# FTDI_GT16.net
KiCad netlist of a schematic drawn in EAGLE
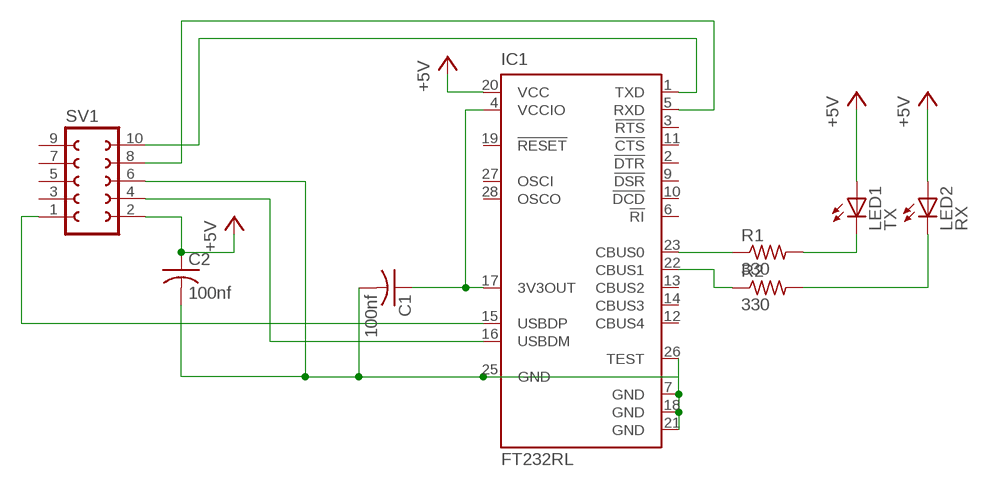
[diagram p0: schematic, sheet 1]

(export (version "E")
  (design (tool "Eeschema 10.0.6"))
  (components
    (comp (ref "C1")
      (value "100nf")
      (footprint "eagle-import:C0805")
      (libsource (lib "eagle-import") (part "C-USC0805"))
    )
    (comp (ref "C2")
      (value "100nf")
      (footprint "eagle-import:C0805")
      (libsource (lib "eagle-import") (part "C-USC0805"))
    )
    (comp (ref "IC1")
      (value "FT232RL")
      (footprint "eagle-import:SSOP28")
      (libsource (lib "eagle-import") (part "FT232RL"))
    )
    (comp (ref "LED1")
      (value "TX")
      (footprint "eagle-import:CHIPLED_0805")
      (libsource (lib "eagle-import") (part "LEDCHIPLED_0805"))
    )
    (comp (ref "LED2")
      (value "RX")
      (footprint "eagle-import:CHIPLED_0805")
      (libsource (lib "eagle-import") (part "LEDCHIPLED_0805"))
    )
    (comp (ref "R1")
      (value "330")
      (footprint "eagle-import:R0805")
      (libsource (lib "eagle-import") (part "R-US_R0805"))
    )
    (comp (ref "R2")
      (value "330")
      (footprint "eagle-import:R0805")
      (libsource (lib "eagle-import") (part "R-US_R0805"))
    )
    (comp (ref "SV1")
      (value "FE05-2")
      (footprint "eagle-import:FE05-2")
      (libsource (lib "eagle-import") (part "FE05-2"))
    )
  )
  (nets
    (net (code "1") (name "+5V") (class "Default")
      (node (ref "C2") (pin "1") (pinfunction "1_1") (pintype "passive"))
      (node (ref "IC1") (pin "20") (pinfunction "VCC_20") (pintype "power_in"))
      (node (ref "LED1") (pin "A") (pinfunction "A_A") (pintype "passive"))
      (node (ref "LED2") (pin "A") (pinfunction "A_A") (pintype "passive"))
      (node (ref "SV1") (pin "2") (pinfunction "2_2") (pintype "passive"))
    )
    (net (code "2") (name "Net-(IC1-3V3OUT)") (class "Default")
      (node (ref "C1") (pin "1") (pinfunction "1_1") (pintype "passive"))
      (node (ref "IC1") (pin "17") (pinfunction "3V3OUT_17") (pintype "output"))
      (node (ref "IC1") (pin "4") (pinfunction "VCCIO_4") (pintype "power_in"))
    )
    (net (code "3") (name "Net-(IC1-CBUS0)") (class "Default")
      (node (ref "IC1") (pin "23") (pinfunction "CBUS0_23") (pintype "bidirectional"))
      (node (ref "R1") (pin "1") (pinfunction "1_1") (pintype "passive"))
    )
    (net (code "4") (name "Net-(IC1-CBUS1)") (class "Default")
      (node (ref "IC1") (pin "22") (pinfunction "CBUS1_22") (pintype "bidirectional"))
      (node (ref "R2") (pin "1") (pinfunction "1_1") (pintype "passive"))
    )
    (net (code "5") (name "Net-(IC1-RXD)") (class "Default")
      (node (ref "IC1") (pin "5") (pinfunction "RXD_5") (pintype "input"))
      (node (ref "SV1") (pin "8") (pinfunction "8_8") (pintype "passive"))
    )
    (net (code "6") (name "Net-(IC1-TEST)") (class "Default")
      (node (ref "C1") (pin "2") (pinfunction "2_2") (pintype "passive"))
      (node (ref "C2") (pin "2") (pinfunction "2_2") (pintype "passive"))
      (node (ref "IC1") (pin "18") (pinfunction "GND_18") (pintype "power_in"))
      (node (ref "IC1") (pin "21") (pinfunction "GND_21") (pintype "power_in"))
      (node (ref "IC1") (pin "25") (pinfunction "GND_25") (pintype "power_in"))
      (node (ref "IC1") (pin "26") (pinfunction "TEST_26") (pintype "input"))
      (node (ref "IC1") (pin "7") (pinfunction "GND_7") (pintype "power_in"))
      (node (ref "SV1") (pin "6") (pinfunction "6_6") (pintype "passive"))
    )
    (net (code "7") (name "Net-(IC1-TXD)") (class "Default")
      (node (ref "IC1") (pin "1") (pinfunction "TXD_1") (pintype "output"))
      (node (ref "SV1") (pin "10") (pinfunction "10_10") (pintype "passive"))
    )
    (net (code "8") (name "Net-(IC1-USBDM)") (class "Default")
      (node (ref "IC1") (pin "16") (pinfunction "USBDM_16") (pintype "bidirectional"))
      (node (ref "SV1") (pin "4") (pinfunction "4_4") (pintype "passive"))
    )
    (net (code "9") (name "Net-(IC1-USBDP)") (class "Default")
      (node (ref "IC1") (pin "15") (pinfunction "USBDP_15") (pintype "bidirectional"))
      (node (ref "SV1") (pin "1") (pinfunction "1_1") (pintype "passive"))
    )
    (net (code "10") (name "Net-(LED1-PadC)") (class "Default")
      (node (ref "LED1") (pin "C") (pinfunction "C_C") (pintype "passive"))
      (node (ref "R1") (pin "2") (pinfunction "2_2") (pintype "passive"))
    )
    (net (code "11") (name "Net-(LED2-PadC)") (class "Default")
      (node (ref "LED2") (pin "C") (pinfunction "C_C") (pintype "passive"))
      (node (ref "R2") (pin "2") (pinfunction "2_2") (pintype "passive"))
    )
    (net (code "12") (name "unconnected-(IC1-CBUS2-Pad13)") (class "Default")
      (node (ref "IC1") (pin "13") (pinfunction "CBUS2_13") (pintype "bidirectional"))
    )
    (net (code "13") (name "unconnected-(IC1-CBUS3-Pad14)") (class "Default")
      (node (ref "IC1") (pin "14") (pinfunction "CBUS3_14") (pintype "bidirectional"))
    )
    (net (code "14") (name "unconnected-(IC1-CBUS4-Pad12)") (class "Default")
      (node (ref "IC1") (pin "12") (pinfunction "CBUS4_12") (pintype "bidirectional"))
    )
    (net (code "15") (name "unconnected-(IC1-OSCI-Pad27)") (class "Default")
      (node (ref "IC1") (pin "27") (pinfunction "OSCI_27") (pintype "input"))
    )
    (net (code "16") (name "unconnected-(IC1-OSCO-Pad28)") (class "Default")
      (node (ref "IC1") (pin "28") (pinfunction "OSCO_28") (pintype "output"))
    )
    (net (code "17") (name "unconnected-(IC1-~{CTS}-Pad11)") (class "Default")
      (node (ref "IC1") (pin "11") (pinfunction "~{CTS}_11") (pintype "input"))
    )
    (net (code "18") (name "unconnected-(IC1-~{DCD}-Pad10)") (class "Default")
      (node (ref "IC1") (pin "10") (pinfunction "~{DCD}_10") (pintype "input"))
    )
    (net (code "19") (name "unconnected-(IC1-~{DSR}-Pad9)") (class "Default")
      (node (ref "IC1") (pin "9") (pinfunction "~{DSR}_9") (pintype "input"))
    )
    (net (code "20") (name "unconnected-(IC1-~{DTR}-Pad2)") (class "Default")
      (node (ref "IC1") (pin "2") (pinfunction "~{DTR}_2") (pintype "output"))
    )
    (net (code "21") (name "unconnected-(IC1-~{RESET}-Pad19)") (class "Default")
      (node (ref "IC1") (pin "19") (pinfunction "~{RESET}_19") (pintype "input"))
    )
    (net (code "22") (name "unconnected-(IC1-~{RI}-Pad6)") (class "Default")
      (node (ref "IC1") (pin "6") (pinfunction "~{RI}_6") (pintype "input"))
    )
    (net (code "23") (name "unconnected-(IC1-~{RTS}-Pad3)") (class "Default")
      (node (ref "IC1") (pin "3") (pinfunction "~{RTS}_3") (pintype "output"))
    )
    (net (code "24") (name "unconnected-(SV1-Pad3)") (class "Default")
      (node (ref "SV1") (pin "3") (pinfunction "3_3") (pintype "passive"))
    )
    (net (code "25") (name "unconnected-(SV1-Pad5)") (class "Default")
      (node (ref "SV1") (pin "5") (pinfunction "5_5") (pintype "passive"))
    )
    (net (code "26") (name "unconnected-(SV1-Pad7)") (class "Default")
      (node (ref "SV1") (pin "7") (pinfunction "7_7") (pintype "passive"))
    )
    (net (code "27") (name "unconnected-(SV1-Pad9)") (class "Default")
      (node (ref "SV1") (pin "9") (pinfunction "9_9") (pintype "passive"))
    )
  )
)
